# 8-SensorsAndJTAG.net
KiCad netlist of a schematic drawn in Altium Designer
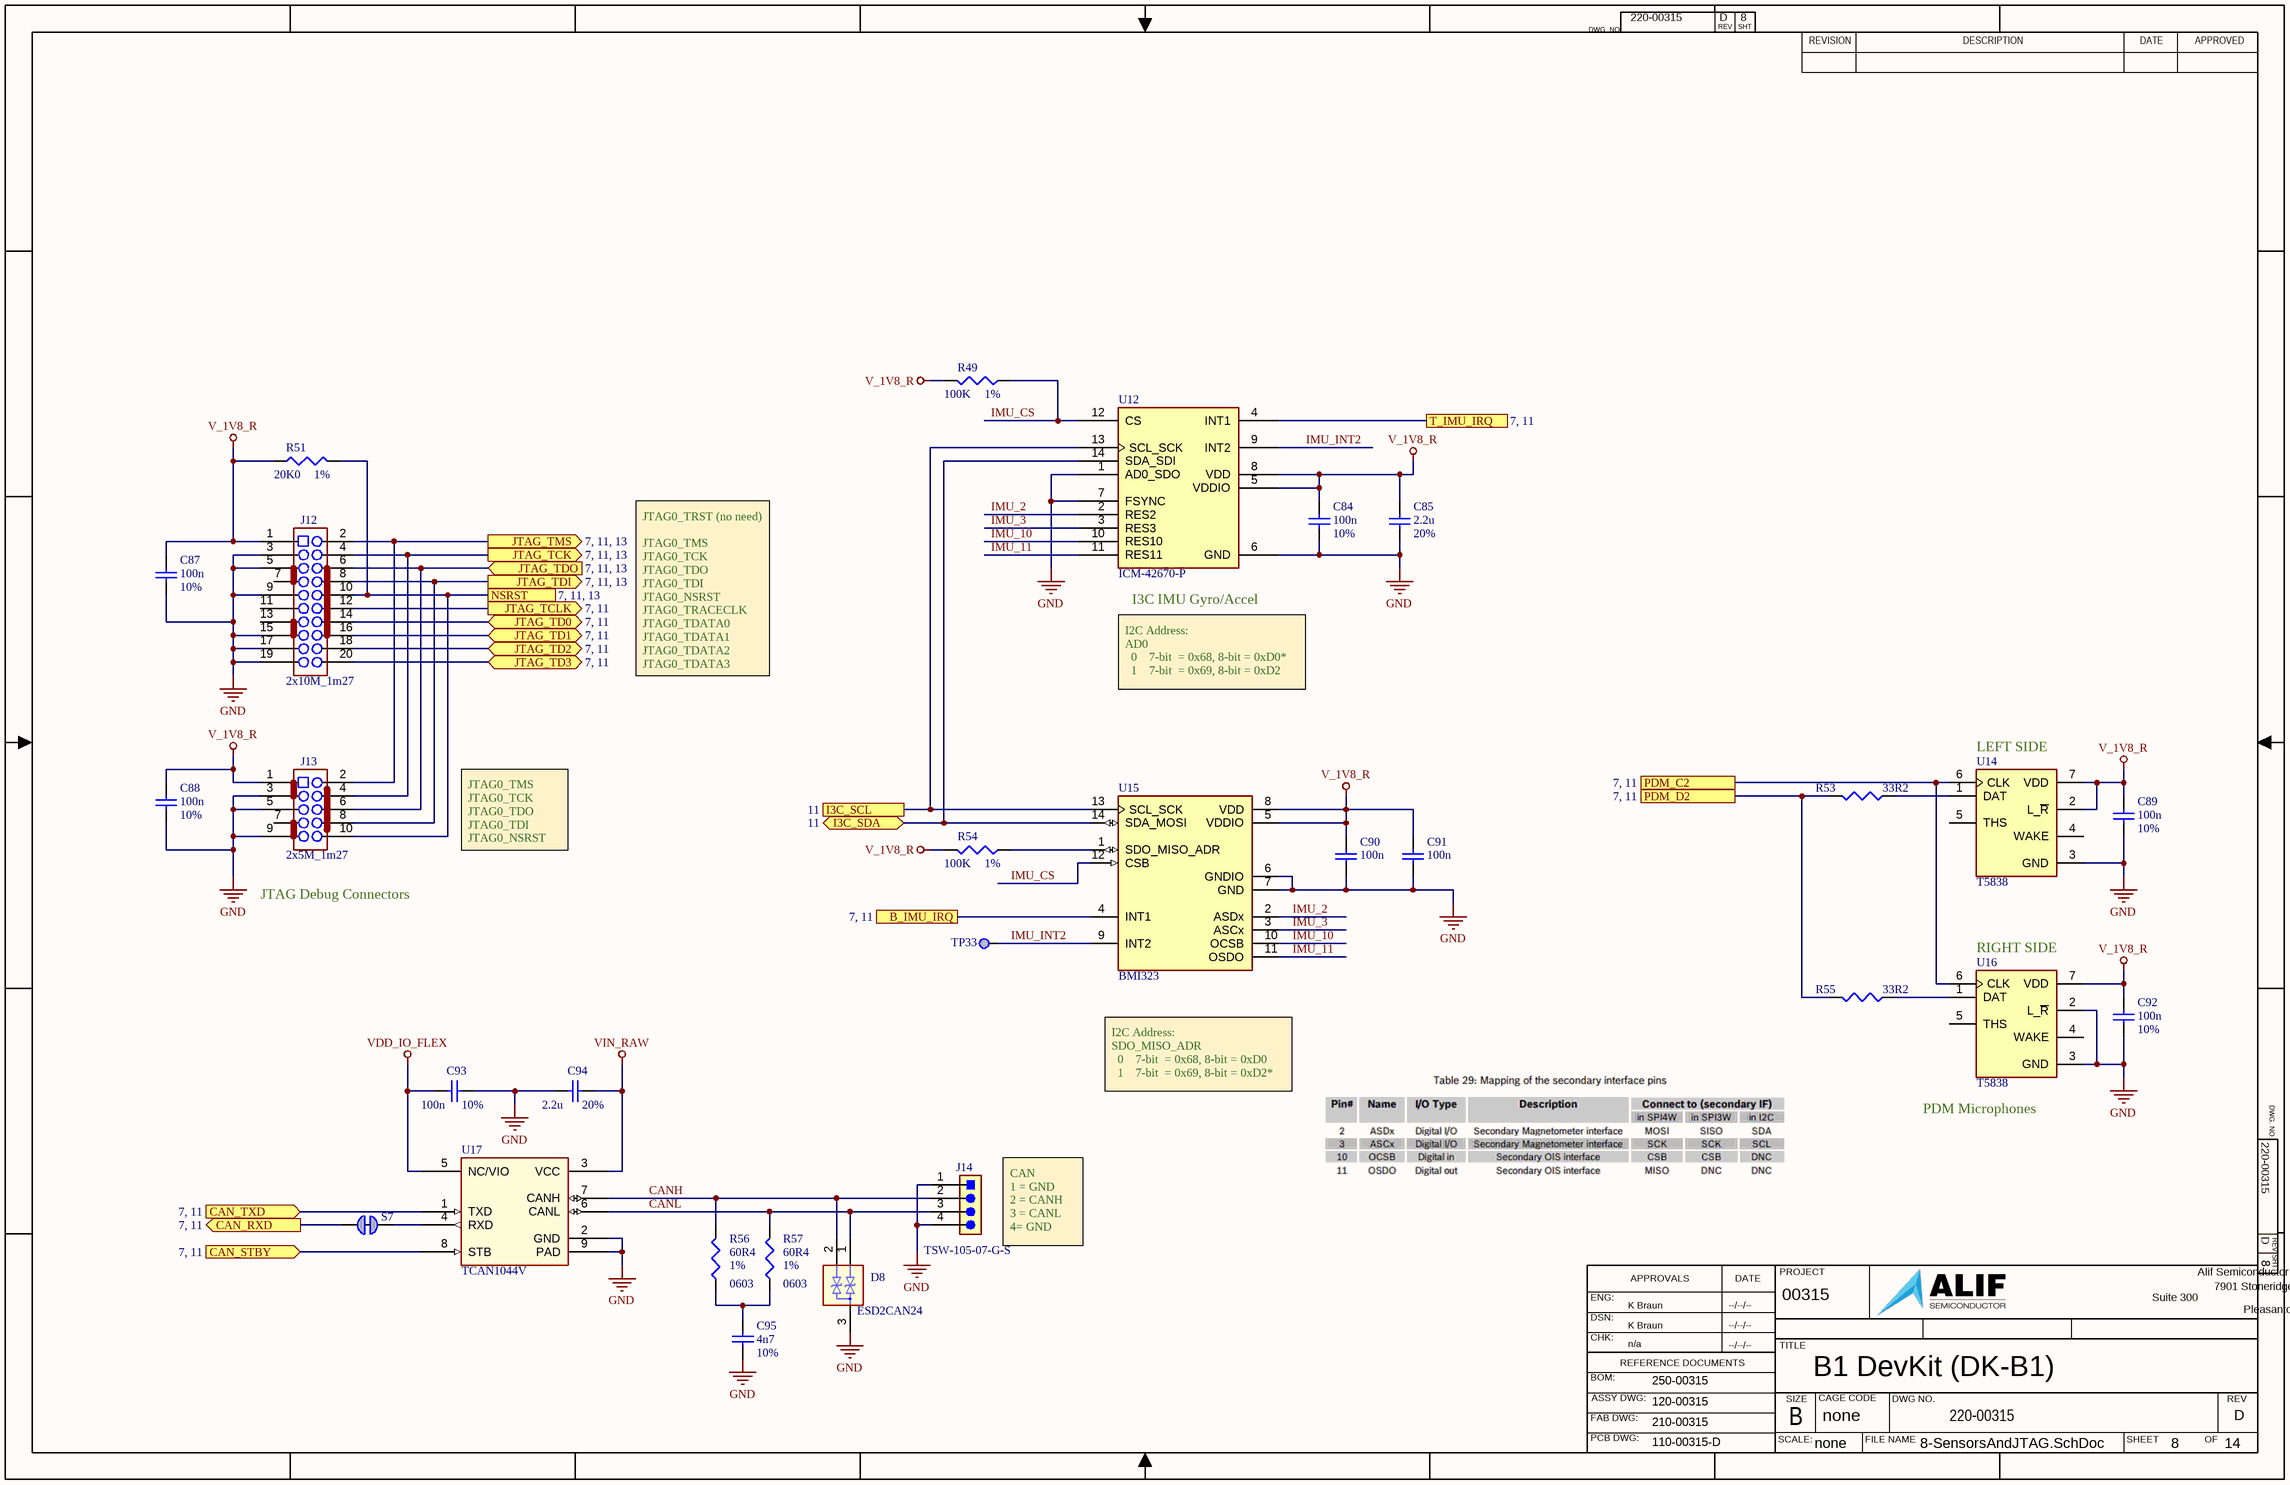
[diagram p0: 8-SensorsAndJTAG.SchDoc]

(export (version "E")
  (design (tool "Eeschema 10.0.6"))
  (components
    (comp (ref "C84")
      (value "100n")
      (footprint "CAPC0402-01")
      (description "Cap,100nF,10%,50V,X7R,0402")
      (fields
        (field (name "VOLTAGE") "50V")
        (field (name "TOLERANCE") "10%")
        (field (name "Comment") "Cap")
        (field (name "PUBLISHER") "Altium Limited")
      )
      (libsource (lib "kb1") (part "Cap"))
    )
    (comp (ref "C85")
      (value "2.2u")
      (footprint "CAPC0402-01")
      (description "Cap,2.2uF,20%,25V,X5R,0402")
      (fields
        (field (name "VOLTAGE") "25V")
        (field (name "TOLERANCE") "20%")
        (field (name "Comment") "Cap_225M25VX5R0402_1")
        (field (name "PUBLISHER") "Altium Limited")
      )
      (libsource (lib "Alif-2") (part "Cap_225M25VX5R0402_1"))
    )
    (comp (ref "C87")
      (value "100n")
      (footprint "CAPC0402-01")
      (description "Cap,100nF,10%,50V,X7R,0402")
      (fields
        (field (name "VOLTAGE") "50V")
        (field (name "TOLERANCE") "10%")
        (field (name "Comment") "Cap")
        (field (name "PUBLISHER") "Altium Limited")
      )
      (libsource (lib "kb1") (part "Cap"))
    )
    (comp (ref "C88")
      (value "100n")
      (footprint "CAPC0402-01")
      (description "Cap,100nF,10%,50V,X7R,0402")
      (fields
        (field (name "VOLTAGE") "50V")
        (field (name "TOLERANCE") "10%")
        (field (name "Comment") "Cap")
        (field (name "PUBLISHER") "Altium Limited")
      )
      (libsource (lib "kb1") (part "Cap"))
    )
    (comp (ref "C89")
      (value "100n")
      (footprint "CAPC0402-01")
      (description "Cap,100nF,10%,50V,X7R,0402")
      (fields
        (field (name "VOLTAGE") "50V")
        (field (name "TOLERANCE") "10%")
        (field (name "Comment") "Cap")
        (field (name "PUBLISHER") "Altium Limited")
      )
      (libsource (lib "kb1") (part "Cap"))
    )
    (comp (ref "C90")
      (value "100n")
      (footprint "CAPC0402-01")
      (description "Cap,100nF,10%,50V,X7R,0402")
      (fields
        (field (name "VOLTAGE") "50V")
        (field (name "TOLERANCE") "10%")
        (field (name "PUBLISHER") "Altium Limited")
      )
      (libsource (lib "kb1") (part "Cap"))
    )
    (comp (ref "C91")
      (value "100n")
      (footprint "CAPC0402-01")
      (description "Cap,100nF,10%,50V,X7R,0402")
      (fields
        (field (name "VOLTAGE") "50V")
        (field (name "TOLERANCE") "10%")
        (field (name "PUBLISHER") "Altium Limited")
      )
      (libsource (lib "kb1") (part "Cap"))
    )
    (comp (ref "C92")
      (value "100n")
      (footprint "CAPC0402-01")
      (description "Cap,100nF,10%,50V,X7R,0402")
      (fields
        (field (name "VOLTAGE") "50V")
        (field (name "TOLERANCE") "10%")
        (field (name "Comment") "Cap")
        (field (name "PUBLISHER") "Altium Limited")
      )
      (libsource (lib "kb1") (part "Cap"))
    )
    (comp (ref "C93")
      (value "100n")
      (footprint "CAPC0402-01")
      (description "Cap,100nF,10%,50V,X7R,0402")
      (fields
        (field (name "VOLTAGE") "50V")
        (field (name "TOLERANCE") "10%")
        (field (name "Comment") "Cap")
        (field (name "PUBLISHER") "Altium Limited")
      )
      (libsource (lib "kb1") (part "Cap"))
    )
    (comp (ref "C94")
      (value "2.2u")
      (footprint "CAPC0402-01")
      (description "Cap,2.2uF,20%,25V,X5R,0402")
      (fields
        (field (name "VOLTAGE") "25V")
        (field (name "TOLERANCE") "20%")
        (field (name "Comment") "Cap_225M25VX5R0402_1")
        (field (name "PUBLISHER") "Altium Limited")
      )
      (libsource (lib "Alif-2") (part "Cap_225M25VX5R0402_1"))
    )
    (comp (ref "C95")
      (value "4n7")
      (footprint "CAPC0402-01")
      (description "Cap,4.7nF,10%,100V,X7R,0402")
      (fields
        (field (name "VOLTAGE") "100V")
        (field (name "TOLERANCE") "10%")
        (field (name "Comment") "Cap")
        (field (name "PUBLISHER") "Altium Limited")
      )
      (libsource (lib "kb1") (part "Cap"))
    )
    (comp (ref "D8")
      (value "ESD2CAN24")
      (footprint "WE-TVS_SOT23-3L")
      (description "Diode,TVS  – High Speed Series, SOT23-3, 2 Channel, 24Vdc, 12pF")
      (libsource (lib "Alif-2") (part "D_ESD_ESD2CAN24DBZRQ1"))
    )
    (comp (ref "J12")
      (value "2x10M_1m27")
      (footprint "SAMTEC_FTSH-110-01-X-DV-007-K")
      (description "Hdr,Male,2x10,1.27mm,Strt,Keyed,Cortex-JTAG")
      (fields (field (name "Comment") "Hdr_M_2X10_1M27_STRT_KEY_CORTEX_1"))
      (libsource (lib "Alif-2") (part "Hdr_M_2X10_1M27_STRT_KEY_CORTEX_1"))
    )
    (comp (ref "J13")
      (value "2x5M_1m27")
      (footprint "SAMTEC_FTSH-105-01-DV-007-K")
      (description "Hdr,Male,2x5,1.27mm,Strt,Keyed,Cortex-JTAG")
      (fields (field (name "Comment") "Hdr_M_2X5_1M27_STRT_KEY_CORTEX_1"))
      (libsource (lib "Alif-2") (part "Hdr_M_2X5_1M27_STRT_KEY_CORTEX_1"))
    )
    (comp (ref "J14")
      (value "TSW-105-07-G-S")
      (footprint "CONN_HDR_1X4_STRT_0.100")
      (description "Hdr, 0.025\" SQ Post Header, Thru-hole, Vertical, 2.54 mm Pitch, 4-Pin, Male, RoHS")
      (fields (field (name "MANUFACTURER") "Samtec"))
      (libsource (lib "Alif-2") (part "Hdr_M_1X4_2M54_STRT_UNSHROUD"))
    )
    (comp (ref "R49")
      (value "100K")
      (footprint "RESC0402-01")
      (description "Res,100K,1%,100ppm,0402")
      (fields
        (field (name "TOLERANCE") "1%")
        (field (name "Comment") "Res3")
        (field (name "PUBLISHER") "Altium Limited")
      )
      (libsource (lib "kb1") (part "Res3"))
    )
    (comp (ref "R51")
      (value "20K0")
      (footprint "RESC0402-01")
      (description "Res,20K0,1%,100ppm,0402")
      (fields
        (field (name "TOLERANCE") "1%")
        (field (name "Comment") "Res3")
        (field (name "PUBLISHER") "Altium Limited")
      )
      (libsource (lib "kb1") (part "Res3"))
    )
    (comp (ref "R53")
      (value "33R2")
      (footprint "RESC0402-01")
      (description "Res,33R2,1%,100ppm,0402")
      (fields
        (field (name "TOLERANCE") "1%")
        (field (name "Comment") "Res3")
        (field (name "PUBLISHER") "Altium Limited")
      )
      (libsource (lib "kb1") (part "Res3"))
    )
    (comp (ref "R54")
      (value "100K")
      (footprint "RESC0402-01")
      (description "Res,100K,1%,100ppm,0402")
      (fields
        (field (name "TOLERANCE") "1%")
        (field (name "Comment") "Res3")
        (field (name "PUBLISHER") "Altium Limited")
      )
      (libsource (lib "kb1") (part "Res3"))
    )
    (comp (ref "R55")
      (value "33R2")
      (footprint "RESC0402-01")
      (description "Res,33R2,1%,100ppm,0402")
      (fields
        (field (name "TOLERANCE") "1%")
        (field (name "Comment") "Res3")
        (field (name "PUBLISHER") "Altium Limited")
      )
      (libsource (lib "kb1") (part "Res3"))
    )
    (comp (ref "R56")
      (value "60R4")
      (footprint "RESC0603-01")
      (description "Res,60R4,1%,100ppm,0603")
      (fields
        (field (name "PCB_FOOTPRINT") "0603")
        (field (name "TOLERANCE") "1%")
        (field (name "Comment") "Res3")
        (field (name "PUBLISHER") "Altium Limited")
      )
      (libsource (lib "kb1") (part "Res3"))
    )
    (comp (ref "R57")
      (value "60R4")
      (footprint "RESC0603-01")
      (description "Res,60R4,1%,100ppm,0603")
      (fields
        (field (name "PCB_FOOTPRINT") "0603")
        (field (name "TOLERANCE") "1%")
        (field (name "Comment") "Res3")
        (field (name "PUBLISHER") "Altium Limited")
      )
      (libsource (lib "kb1") (part "Res3"))
    )
    (comp (ref "S7")
      (value "SolderJumperShorted_Small")
      (footprint "Solderbridge_Shorted")
      (description "DNI,Solderable Jumper,Shorted")
      (fields (field (name "PUBLISHER") "Altium Limited"))
      (libsource (lib "Alif-2") (part "SolderJumperShorted_Small"))
    )
    (comp (ref "TP33")
      (value "TP_SMPAD")
      (footprint "TP_30_RND")
      (description "DNI,Test Point, SMT Pad,--not a BOM item--")
      (libsource (lib "Alif-2") (part "TP_SMPAD"))
    )
    (comp (ref "U12")
      (value "ICM-42670-P_1")
      (footprint "IC_ICM-42670-P")
      (description "IC, IMU Gyro & Accel, I3C, 1.8V, LGA14")
      (fields (field (name "MANUFACTURER PART NUMBER 1") "ICM-42670-P"))
      (libsource (lib "Alif-2") (part "ICM-42670-P_1"))
    )
    (comp (ref "U14")
      (value "T5838")
      (footprint "MIC_T5838")
      (description "IC,Microphone,PDM,Bottom Port,Sens -37db,SNR 68dbA,AOP 13db SPL,1.8V")
      (libsource (lib "Alif-2") (part "MIC_T5838"))
    )
    (comp (ref "U15")
      (value "BMI323")
      (footprint "PQFN50P250X300X88-14N")
      (description "IC,IMU,6 Axis Sensor I3C, SPI, LGA14")
      (fields (field (name "MF") "Bosch"))
      (libsource (lib "Alif-2") (part "IC_IMU_BMI323"))
    )
    (comp (ref "U16")
      (value "T5838")
      (footprint "MIC_T5838")
      (description "IC,Microphone,PDM,Bottom Port,Sens -37db,SNR 68dbA,AOP 13db SPL,1.8V")
      (libsource (lib "Alif-2") (part "MIC_T5838"))
    )
    (comp (ref "U17")
      (value "TCAN1044V")
      (footprint "DFN8_2x3_SON8_DRB_TEX-M")
      (description "IC, CAN Transceiver, 1.7V-5.5V, DFN8(2x3)")
      (libsource (lib "Alif-2") (part "IC_CAN_TCAN1044VDRBRQ1"))
    )
  )
  (nets
    (net (code "1") (name "/B_IMU_IRQ") (class "Default")
      (node (ref "U15") (pin "4") (pinfunction "INT1_4") (pintype "open_collector"))
    )
    (net (code "2") (name "/CANH") (class "Default")
      (node (ref "D8") (pin "2") (pinfunction "2_2") (pintype "passive"))
      (node (ref "J14") (pin "2") (pinfunction "2_2") (pintype "passive"))
      (node (ref "R56") (pin "2") (pinfunction "2_2") (pintype "passive"))
      (node (ref "U17") (pin "7") (pinfunction "CANH_7") (pintype "bidirectional"))
    )
    (net (code "3") (name "/CANL") (class "Default")
      (node (ref "D8") (pin "1") (pinfunction "1_1") (pintype "passive"))
      (node (ref "J14") (pin "3") (pinfunction "3_3") (pintype "passive"))
      (node (ref "R57") (pin "2") (pinfunction "2_2") (pintype "passive"))
      (node (ref "U17") (pin "6") (pinfunction "CANL_6") (pintype "bidirectional"))
    )
    (net (code "4") (name "/CAN_RXD") (class "Default")
      (node (ref "S7") (pin "1") (pinfunction "1_1") (pintype "passive"))
    )
    (net (code "5") (name "/CAN_STBY") (class "Default")
      (node (ref "U17") (pin "8") (pinfunction "STB_8") (pintype "input"))
    )
    (net (code "6") (name "/CAN_TXD") (class "Default")
      (node (ref "U17") (pin "1") (pinfunction "TXD_1") (pintype "input"))
    )
    (net (code "7") (name "/I3C_SCL") (class "Default")
      (node (ref "U12") (pin "13") (pinfunction "SCL_SCK_13") (pintype "passive"))
      (node (ref "U15") (pin "13") (pinfunction "SCL_SCK_13") (pintype "passive"))
    )
    (net (code "8") (name "/I3C_SDA") (class "Default")
      (node (ref "U12") (pin "14") (pinfunction "SDA_SDI_14") (pintype "passive"))
      (node (ref "U15") (pin "14") (pinfunction "SDA_MOSI_14") (pintype "bidirectional"))
    )
    (net (code "9") (name "/IMU_2") (class "Default")
      (node (ref "U12") (pin "2") (pinfunction "RES2_2") (pintype "passive"))
      (node (ref "U15") (pin "2") (pinfunction "ASDx_2") (pintype "passive"))
    )
    (net (code "10") (name "/IMU_3") (class "Default")
      (node (ref "U12") (pin "3") (pinfunction "RES3_3") (pintype "passive"))
      (node (ref "U15") (pin "3") (pinfunction "ASCx_3") (pintype "passive"))
    )
    (net (code "11") (name "/IMU_10") (class "Default")
      (node (ref "U12") (pin "10") (pinfunction "RES10_10") (pintype "passive"))
      (node (ref "U15") (pin "10") (pinfunction "OCSB_10") (pintype "passive"))
    )
    (net (code "12") (name "/IMU_11") (class "Default")
      (node (ref "U12") (pin "11") (pinfunction "RES11_11") (pintype "passive"))
      (node (ref "U15") (pin "11") (pinfunction "OSDO_11") (pintype "passive"))
    )
    (net (code "13") (name "/IMU_CS") (class "Default")
      (node (ref "R49") (pin "1") (pinfunction "1_1") (pintype "passive"))
      (node (ref "U12") (pin "12") (pinfunction "CS_12") (pintype "passive"))
      (node (ref "U15") (pin "12") (pinfunction "CSB_12") (pintype "input"))
    )
    (net (code "14") (name "/IMU_INT2") (class "Default")
      (node (ref "TP33") (pin "1") (pinfunction "1_1") (pintype "passive"))
      (node (ref "U12") (pin "9") (pinfunction "INT2_9") (pintype "passive"))
      (node (ref "U15") (pin "9") (pinfunction "INT2_9") (pintype "open_collector"))
    )
    (net (code "15") (name "/JTAG_TCK") (class "Default")
      (node (ref "J12") (pin "4") (pinfunction "4_4") (pintype "passive"))
      (node (ref "J13") (pin "4") (pinfunction "4_4") (pintype "passive"))
    )
    (net (code "16") (name "/JTAG_TCLK") (class "Default")
      (node (ref "J12") (pin "12") (pinfunction "12_12") (pintype "passive"))
    )
    (net (code "17") (name "/JTAG_TD0") (class "Default")
      (node (ref "J12") (pin "14") (pinfunction "14_14") (pintype "passive"))
    )
    (net (code "18") (name "/JTAG_TD1") (class "Default")
      (node (ref "J12") (pin "16") (pinfunction "16_16") (pintype "passive"))
    )
    (net (code "19") (name "/JTAG_TD2") (class "Default")
      (node (ref "J12") (pin "18") (pinfunction "18_18") (pintype "passive"))
    )
    (net (code "20") (name "/JTAG_TD3") (class "Default")
      (node (ref "J12") (pin "20") (pinfunction "20_20") (pintype "passive"))
    )
    (net (code "21") (name "/JTAG_TDI") (class "Default")
      (node (ref "J12") (pin "8") (pinfunction "8_8") (pintype "passive"))
      (node (ref "J13") (pin "8") (pinfunction "8_8") (pintype "passive"))
    )
    (net (code "22") (name "/JTAG_TDO") (class "Default")
      (node (ref "J12") (pin "6") (pinfunction "6_6") (pintype "passive"))
      (node (ref "J13") (pin "6") (pinfunction "6_6") (pintype "passive"))
    )
    (net (code "23") (name "/JTAG_TMS") (class "Default")
      (node (ref "J12") (pin "2") (pinfunction "2_2") (pintype "passive"))
      (node (ref "J13") (pin "2") (pinfunction "2_2") (pintype "passive"))
    )
    (net (code "24") (name "/NSRST") (class "Default")
      (node (ref "J12") (pin "10") (pinfunction "10_10") (pintype "passive"))
      (node (ref "J13") (pin "10") (pinfunction "10_10") (pintype "passive"))
      (node (ref "R51") (pin "2") (pinfunction "2_2") (pintype "passive"))
    )
    (net (code "25") (name "/PDM_C2") (class "Default")
      (node (ref "U14") (pin "6") (pinfunction "CLK_6") (pintype "passive"))
      (node (ref "U16") (pin "6") (pinfunction "CLK_6") (pintype "passive"))
    )
    (net (code "26") (name "/PDM_D2") (class "Default")
      (node (ref "R53") (pin "2") (pinfunction "2_2") (pintype "passive"))
      (node (ref "R55") (pin "2") (pinfunction "2_2") (pintype "passive"))
    )
    (net (code "27") (name "/T_IMU_IRQ") (class "Default")
      (node (ref "U12") (pin "4") (pinfunction "INT1_4") (pintype "passive"))
    )
    (net (code "28") (name "GND") (class "Default")
      (node (ref "C84") (pin "2") (pinfunction "2_2") (pintype "passive"))
      (node (ref "C85") (pin "1") (pinfunction "1_1") (pintype "passive"))
      (node (ref "C87") (pin "2") (pinfunction "2_2") (pintype "passive"))
      (node (ref "C88") (pin "2") (pinfunction "2_2") (pintype "passive"))
      (node (ref "C89") (pin "2") (pinfunction "2_2") (pintype "passive"))
      (node (ref "C90") (pin "2") (pinfunction "2_2") (pintype "passive"))
      (node (ref "C91") (pin "2") (pinfunction "2_2") (pintype "passive"))
      (node (ref "C92") (pin "2") (pinfunction "2_2") (pintype "passive"))
      (node (ref "C93") (pin "1") (pinfunction "1_1") (pintype "passive"))
      (node (ref "C94") (pin "2") (pinfunction "2_2") (pintype "passive"))
      (node (ref "C95") (pin "1") (pinfunction "1_1") (pintype "passive"))
      (node (ref "D8") (pin "3") (pinfunction "3_3") (pintype "passive"))
      (node (ref "J12") (pin "15") (pinfunction "15_15") (pintype "passive"))
      (node (ref "J12") (pin "17") (pinfunction "17_17") (pintype "passive"))
      (node (ref "J12") (pin "19") (pinfunction "19_19") (pintype "passive"))
      (node (ref "J12") (pin "3") (pinfunction "3_3") (pintype "passive"))
      (node (ref "J12") (pin "5") (pinfunction "5_5") (pintype "passive"))
      (node (ref "J12") (pin "9") (pinfunction "9_9") (pintype "passive"))
      (node (ref "J13") (pin "3") (pinfunction "3_3") (pintype "passive"))
      (node (ref "J13") (pin "5") (pinfunction "5_5") (pintype "passive"))
      (node (ref "J13") (pin "9") (pinfunction "9_9") (pintype "passive"))
      (node (ref "J14") (pin "1") (pinfunction "1_1") (pintype "passive"))
      (node (ref "J14") (pin "4") (pinfunction "43_4") (pintype "passive"))
      (node (ref "U12") (pin "1") (pinfunction "AD0_SDO_1") (pintype "passive"))
      (node (ref "U12") (pin "6") (pinfunction "GND_6") (pintype "passive"))
      (node (ref "U12") (pin "7") (pinfunction "FSYNC_7") (pintype "passive"))
      (node (ref "U14") (pin "3") (pinfunction "GND_3") (pintype "passive"))
      (node (ref "U15") (pin "6") (pinfunction "GNDIO_6") (pintype "power_in"))
      (node (ref "U15") (pin "7") (pinfunction "GND_7") (pintype "power_in"))
      (node (ref "U16") (pin "2") (pinfunction "L_~{R}_2") (pintype "passive"))
      (node (ref "U16") (pin "3") (pinfunction "GND_3") (pintype "passive"))
      (node (ref "U17") (pin "2") (pinfunction "GND_2") (pintype "power_in"))
      (node (ref "U17") (pin "9") (pinfunction "PAD_9") (pintype "power_in"))
    )
    (net (code "29") (name "Net-(C95-Pad2)") (class "Default")
      (node (ref "C95") (pin "2") (pinfunction "2_2") (pintype "passive"))
      (node (ref "R56") (pin "1") (pinfunction "1_1") (pintype "passive"))
      (node (ref "R57") (pin "1") (pinfunction "1_1") (pintype "passive"))
    )
    (net (code "30") (name "Net-(U14-DAT)") (class "Default")
      (node (ref "R53") (pin "1") (pinfunction "1_1") (pintype "passive"))
      (node (ref "U14") (pin "1") (pinfunction "DAT_1") (pintype "passive"))
    )
    (net (code "31") (name "Net-(U15-SDO_MISO_ADR)") (class "Default")
      (node (ref "R54") (pin "1") (pinfunction "1_1") (pintype "passive"))
      (node (ref "U15") (pin "1") (pinfunction "SDO_MISO_ADR_1") (pintype "bidirectional"))
    )
    (net (code "32") (name "Net-(U16-DAT)") (class "Default")
      (node (ref "R55") (pin "1") (pinfunction "1_1") (pintype "passive"))
      (node (ref "U16") (pin "1") (pinfunction "DAT_1") (pintype "passive"))
    )
    (net (code "33") (name "Net-(U17-RXD)") (class "Default")
      (node (ref "S7") (pin "2") (pinfunction "2_2") (pintype "passive"))
      (node (ref "U17") (pin "4") (pinfunction "RXD_4") (pintype "output"))
    )
    (net (code "34") (name "VDD_IO_FLEX") (class "Default")
      (node (ref "C93") (pin "2") (pinfunction "2_2") (pintype "passive"))
      (node (ref "U17") (pin "5") (pinfunction "NC/VIO_5") (pintype "passive"))
    )
    (net (code "35") (name "VIN_RAW") (class "Default")
      (node (ref "C94") (pin "1") (pinfunction "1_1") (pintype "passive"))
      (node (ref "U17") (pin "3") (pinfunction "VCC_3") (pintype "power_in"))
    )
    (net (code "36") (name "V_1V8_R") (class "Default")
      (node (ref "C84") (pin "1") (pinfunction "1_1") (pintype "passive"))
      (node (ref "C85") (pin "2") (pinfunction "2_2") (pintype "passive"))
      (node (ref "C87") (pin "1") (pinfunction "1_1") (pintype "passive"))
      (node (ref "C88") (pin "1") (pinfunction "1_1") (pintype "passive"))
      (node (ref "C89") (pin "1") (pinfunction "1_1") (pintype "passive"))
      (node (ref "C90") (pin "1") (pinfunction "1_1") (pintype "passive"))
      (node (ref "C91") (pin "1") (pinfunction "1_1") (pintype "passive"))
      (node (ref "C92") (pin "1") (pinfunction "1_1") (pintype "passive"))
      (node (ref "J12") (pin "1") (pinfunction "1_1") (pintype "passive"))
      (node (ref "J13") (pin "1") (pinfunction "1_1") (pintype "passive"))
      (node (ref "R49") (pin "2") (pinfunction "2_2") (pintype "passive"))
      (node (ref "R51") (pin "1") (pinfunction "1_1") (pintype "passive"))
      (node (ref "R54") (pin "2") (pinfunction "2_2") (pintype "passive"))
      (node (ref "U12") (pin "5") (pinfunction "VDDIO_5") (pintype "passive"))
      (node (ref "U12") (pin "8") (pinfunction "VDD_8") (pintype "passive"))
      (node (ref "U14") (pin "2") (pinfunction "L_~{R}_2") (pintype "passive"))
      (node (ref "U14") (pin "7") (pinfunction "VDD_7") (pintype "passive"))
      (node (ref "U15") (pin "5") (pinfunction "VDDIO_5") (pintype "power_in"))
      (node (ref "U15") (pin "8") (pinfunction "VDD_8") (pintype "power_in"))
      (node (ref "U16") (pin "7") (pinfunction "VDD_7") (pintype "passive"))
    )
    (net (code "37") (name "unconnected-(J12-Pad7)") (class "Default")
      (node (ref "J12") (pin "7") (pinfunction "7_7") (pintype "passive"))
    )
    (net (code "38") (name "unconnected-(J12-Pad11)") (class "Default")
      (node (ref "J12") (pin "11") (pinfunction "11_11") (pintype "passive"))
    )
    (net (code "39") (name "unconnected-(J12-Pad13)") (class "Default")
      (node (ref "J12") (pin "13") (pinfunction "13_13") (pintype "passive"))
    )
    (net (code "40") (name "unconnected-(J13-Pad7)") (class "Default")
      (node (ref "J13") (pin "7") (pinfunction "7_7") (pintype "passive"))
    )
    (net (code "41") (name "unconnected-(U14-THS-Pad5)") (class "Default")
      (node (ref "U14") (pin "5") (pinfunction "THS_5") (pintype "passive"))
    )
    (net (code "42") (name "unconnected-(U14-WAKE-Pad4)") (class "Default")
      (node (ref "U14") (pin "4") (pinfunction "WAKE_4") (pintype "power_in"))
    )
    (net (code "43") (name "unconnected-(U16-THS-Pad5)") (class "Default")
      (node (ref "U16") (pin "5") (pinfunction "THS_5") (pintype "passive"))
    )
    (net (code "44") (name "unconnected-(U16-WAKE-Pad4)") (class "Default")
      (node (ref "U16") (pin "4") (pinfunction "WAKE_4") (pintype "power_in"))
    )
  )
)
